# PQ60_EPS_FV4.net
KiCad netlist of a schematic drawn in EAGLE
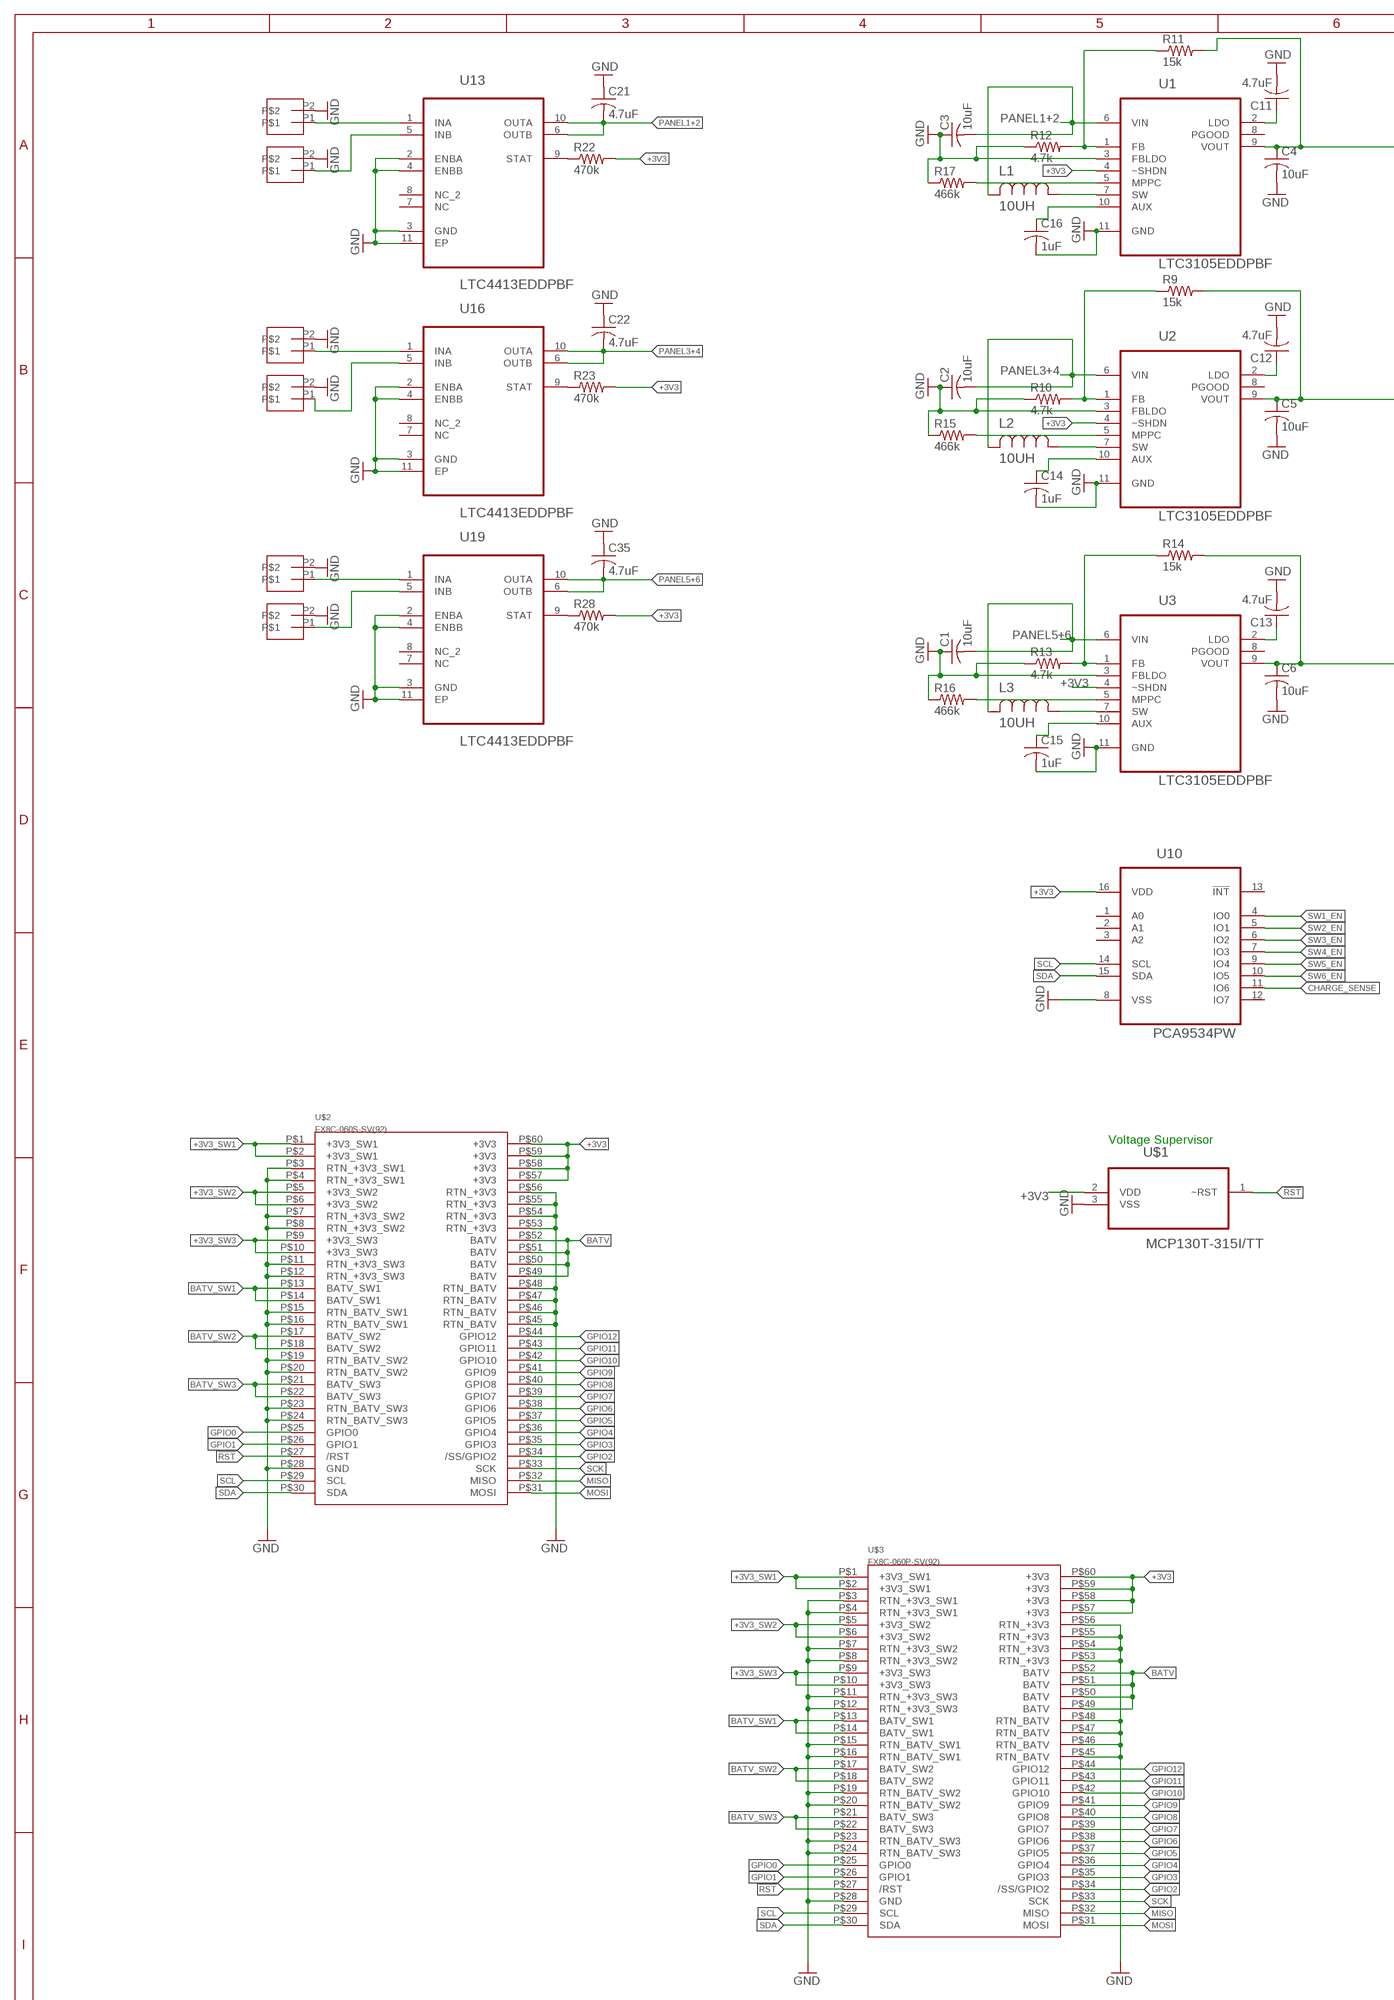
[diagram p0: schematic, sheet 1, part 1 of 2]
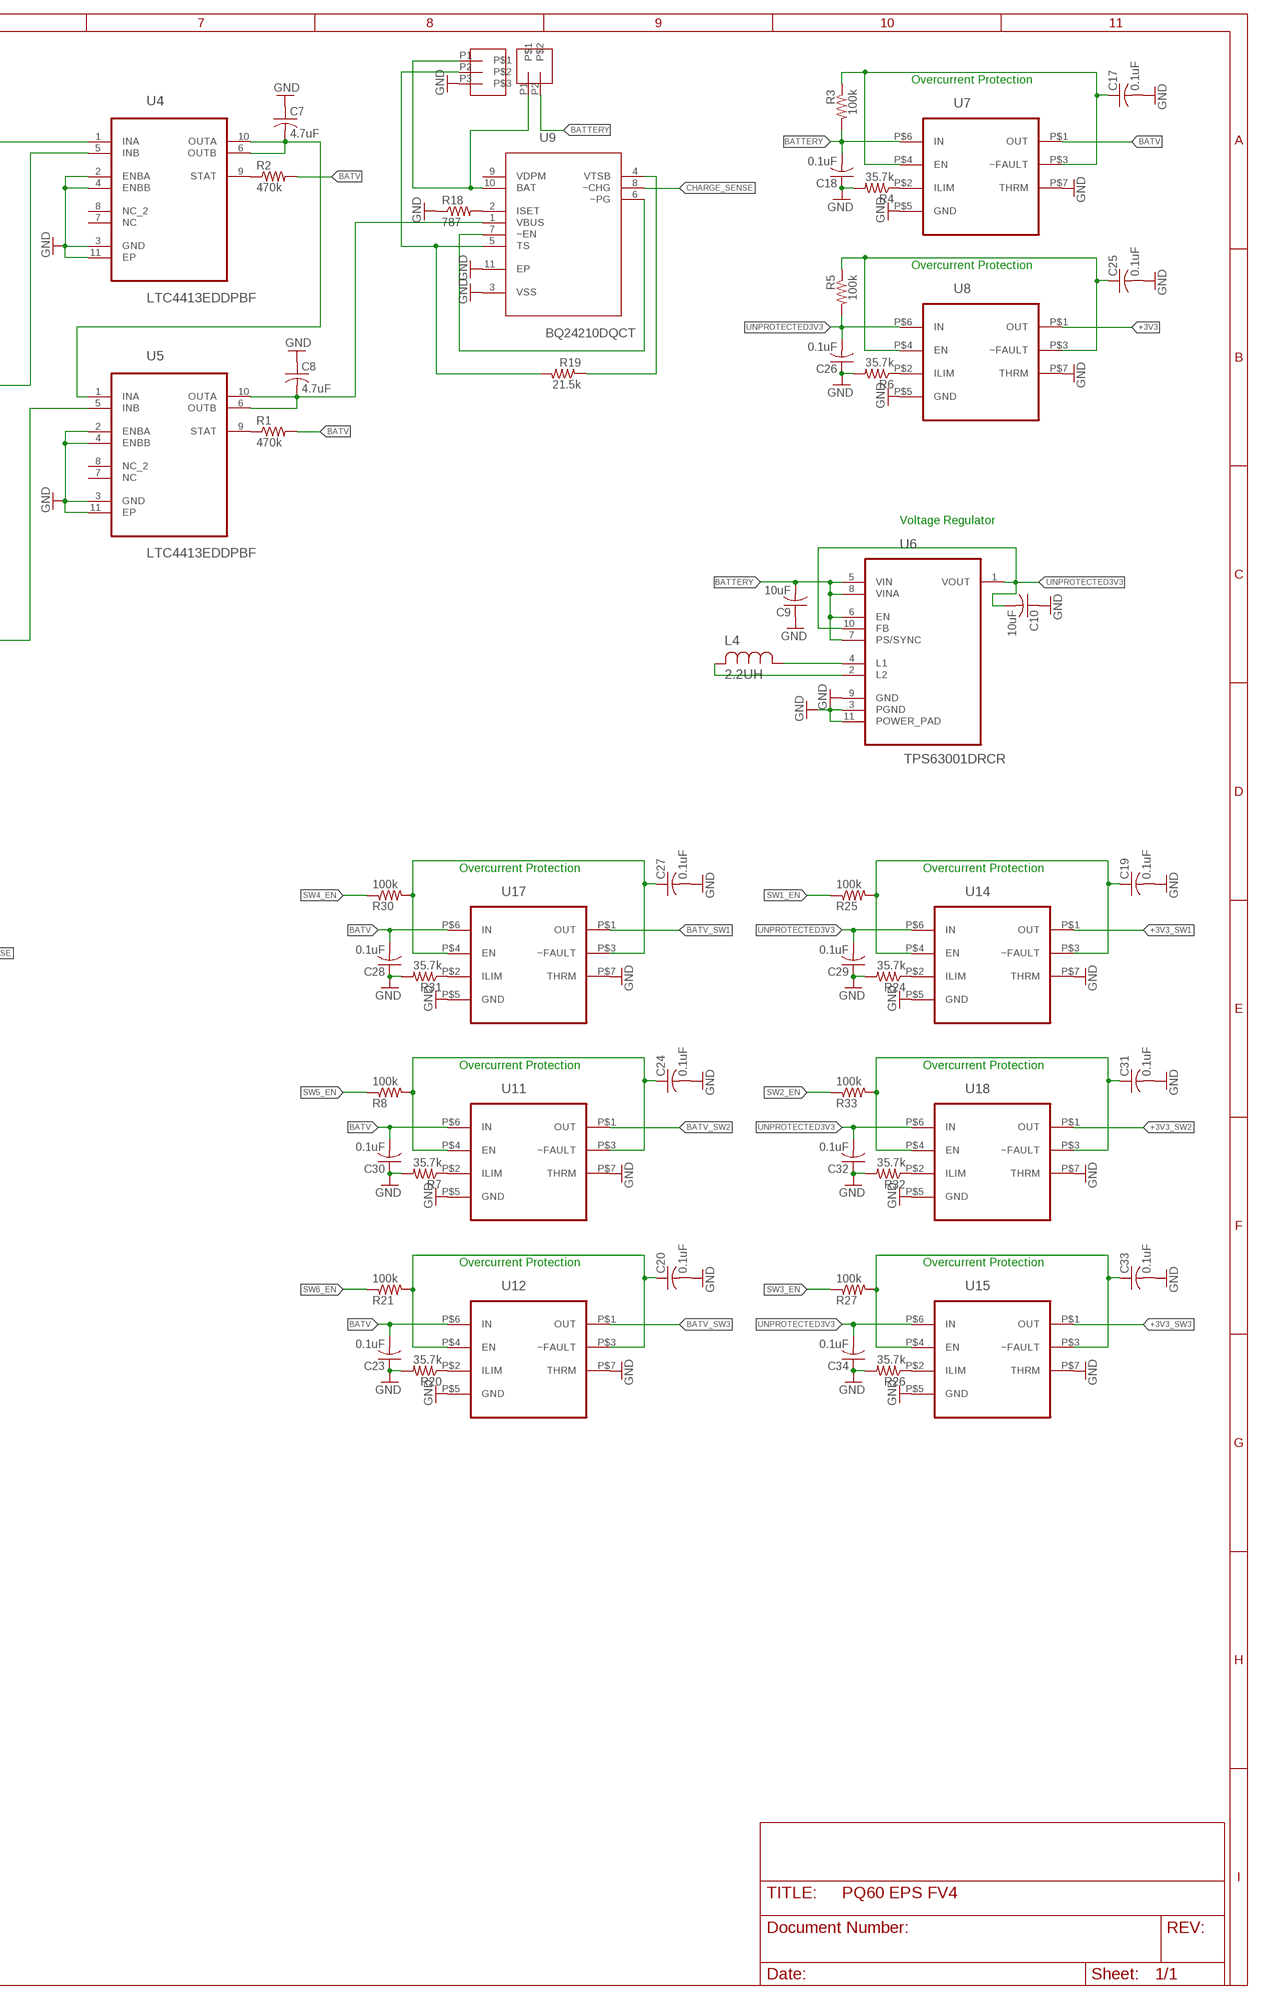
[diagram p1: schematic, sheet 1, part 2 of 2]

(export (version "E")
  (design (tool "Eeschema 10.0.6"))
  (components
    (comp (ref "C1")
      (value "10uF")
      (footprint "eagle-import:C0805")
      (libsource (lib "eagle-import") (part "C-USC0805"))
    )
    (comp (ref "C2")
      (value "10uF")
      (footprint "eagle-import:C0805")
      (libsource (lib "eagle-import") (part "C-USC0805"))
    )
    (comp (ref "C3")
      (value "10uF")
      (footprint "eagle-import:C0805")
      (libsource (lib "eagle-import") (part "C-USC0805"))
    )
    (comp (ref "C4")
      (value "10uF")
      (footprint "eagle-import:C0805")
      (libsource (lib "eagle-import") (part "C-USC0805"))
    )
    (comp (ref "C5")
      (value "10uF")
      (footprint "eagle-import:C0805")
      (libsource (lib "eagle-import") (part "C-USC0805"))
    )
    (comp (ref "C6")
      (value "10uF")
      (footprint "eagle-import:C0805")
      (libsource (lib "eagle-import") (part "C-USC0805"))
    )
    (comp (ref "C7")
      (value "4.7uF")
      (footprint "eagle-import:C0805")
      (libsource (lib "eagle-import") (part "C-USC0805"))
    )
    (comp (ref "C8")
      (value "4.7uF")
      (footprint "eagle-import:C0805")
      (libsource (lib "eagle-import") (part "C-USC0805"))
    )
    (comp (ref "C9")
      (value "10uF")
      (footprint "eagle-import:C0805")
      (libsource (lib "eagle-import") (part "C-USC0805"))
    )
    (comp (ref "C10")
      (value "10uF")
      (footprint "eagle-import:C0805")
      (libsource (lib "eagle-import") (part "C-USC0805"))
    )
    (comp (ref "C11")
      (value "4.7uF")
      (footprint "eagle-import:C0805")
      (libsource (lib "eagle-import") (part "C-USC0805"))
    )
    (comp (ref "C12")
      (value "4.7uF")
      (footprint "eagle-import:C0805")
      (libsource (lib "eagle-import") (part "C-USC0805"))
    )
    (comp (ref "C13")
      (value "4.7uF")
      (footprint "eagle-import:C0805")
      (libsource (lib "eagle-import") (part "C-USC0805"))
    )
    (comp (ref "C14")
      (value "1uF")
      (footprint "eagle-import:C0805")
      (libsource (lib "eagle-import") (part "C-USC0805"))
    )
    (comp (ref "C15")
      (value "1uF")
      (footprint "eagle-import:C0805")
      (libsource (lib "eagle-import") (part "C-USC0805"))
    )
    (comp (ref "C16")
      (value "1uF")
      (footprint "eagle-import:C0805")
      (libsource (lib "eagle-import") (part "C-USC0805"))
    )
    (comp (ref "C17")
      (value "0.1uF")
      (footprint "eagle-import:C0805")
      (libsource (lib "eagle-import") (part "C-USC0805"))
    )
    (comp (ref "C18")
      (value "0.1uF")
      (footprint "eagle-import:C0805")
      (libsource (lib "eagle-import") (part "C-USC0805"))
    )
    (comp (ref "C19")
      (value "0.1uF")
      (footprint "eagle-import:C0805")
      (libsource (lib "eagle-import") (part "C-USC0805"))
    )
    (comp (ref "C20")
      (value "0.1uF")
      (footprint "eagle-import:C0805")
      (libsource (lib "eagle-import") (part "C-USC0805"))
    )
    (comp (ref "C21")
      (value "4.7uF")
      (footprint "eagle-import:C0805")
      (libsource (lib "eagle-import") (part "C-USC0805"))
    )
    (comp (ref "C22")
      (value "4.7uF")
      (footprint "eagle-import:C0805")
      (libsource (lib "eagle-import") (part "C-USC0805"))
    )
    (comp (ref "C23")
      (value "0.1uF")
      (footprint "eagle-import:C0805")
      (libsource (lib "eagle-import") (part "C-USC0805"))
    )
    (comp (ref "C24")
      (value "0.1uF")
      (footprint "eagle-import:C0805")
      (libsource (lib "eagle-import") (part "C-USC0805"))
    )
    (comp (ref "C25")
      (value "0.1uF")
      (footprint "eagle-import:C0805")
      (libsource (lib "eagle-import") (part "C-USC0805"))
    )
    (comp (ref "C26")
      (value "0.1uF")
      (footprint "eagle-import:C0805")
      (libsource (lib "eagle-import") (part "C-USC0805"))
    )
    (comp (ref "C27")
      (value "0.1uF")
      (footprint "eagle-import:C0805")
      (libsource (lib "eagle-import") (part "C-USC0805"))
    )
    (comp (ref "C28")
      (value "0.1uF")
      (footprint "eagle-import:C0805")
      (libsource (lib "eagle-import") (part "C-USC0805"))
    )
    (comp (ref "C29")
      (value "0.1uF")
      (footprint "eagle-import:C0805")
      (libsource (lib "eagle-import") (part "C-USC0805"))
    )
    (comp (ref "C30")
      (value "0.1uF")
      (footprint "eagle-import:C0805")
      (libsource (lib "eagle-import") (part "C-USC0805"))
    )
    (comp (ref "C31")
      (value "0.1uF")
      (footprint "eagle-import:C0805")
      (libsource (lib "eagle-import") (part "C-USC0805"))
    )
    (comp (ref "C32")
      (value "0.1uF")
      (footprint "eagle-import:C0805")
      (libsource (lib "eagle-import") (part "C-USC0805"))
    )
    (comp (ref "C33")
      (value "0.1uF")
      (footprint "eagle-import:C0805")
      (libsource (lib "eagle-import") (part "C-USC0805"))
    )
    (comp (ref "C34")
      (value "0.1uF")
      (footprint "eagle-import:C0805")
      (libsource (lib "eagle-import") (part "C-USC0805"))
    )
    (comp (ref "C35")
      (value "4.7uF")
      (footprint "eagle-import:C0805")
      (libsource (lib "eagle-import") (part "C-USC0805"))
    )
    (comp (ref "L1")
      (value "10UH")
      (footprint "eagle-import:IND_ELL6XH")
      (fields (field (name "MPN") "ELL6SH100M"))
      (libsource (lib "eagle-import") (part "ELL-6XH6SH100M"))
    )
    (comp (ref "L2")
      (value "10UH")
      (footprint "eagle-import:IND_ELL6XH")
      (fields (field (name "MPN") "ELL6SH100M"))
      (libsource (lib "eagle-import") (part "ELL-6XH6SH100M"))
    )
    (comp (ref "L3")
      (value "10UH")
      (footprint "eagle-import:IND_ELL6XH")
      (fields (field (name "MPN") "ELL6SH100M"))
      (libsource (lib "eagle-import") (part "ELL-6XH6SH100M"))
    )
    (comp (ref "L4")
      (value "2.2UH")
      (footprint "eagle-import:IND_ELL3FU")
      (fields (field (name "MPN") "ELL3FU2R2N") (field (name "TOLERANCE") "±30 %"))
      (libsource (lib "eagle-import") (part "ELL-3FU3FU2R2N"))
    )
    (comp (ref "R1")
      (value "470k")
      (footprint "eagle-import:R0805")
      (libsource (lib "eagle-import") (part "R-US_R0805"))
    )
    (comp (ref "R2")
      (value "470k")
      (footprint "eagle-import:R0805")
      (libsource (lib "eagle-import") (part "R-US_R0805"))
    )
    (comp (ref "R3")
      (value "100k")
      (footprint "eagle-import:R0805")
      (libsource (lib "eagle-import") (part "R-US_R0805"))
    )
    (comp (ref "R4")
      (value "35.7k")
      (footprint "eagle-import:R0805")
      (libsource (lib "eagle-import") (part "R-US_R0805"))
    )
    (comp (ref "R5")
      (value "100k")
      (footprint "eagle-import:R0805")
      (libsource (lib "eagle-import") (part "R-US_R0805"))
    )
    (comp (ref "R6")
      (value "35.7k")
      (footprint "eagle-import:R0805")
      (libsource (lib "eagle-import") (part "R-US_R0805"))
    )
    (comp (ref "R7")
      (value "35.7k")
      (footprint "eagle-import:R0805")
      (libsource (lib "eagle-import") (part "R-US_R0805"))
    )
    (comp (ref "R8")
      (value "100k")
      (footprint "eagle-import:R0805")
      (libsource (lib "eagle-import") (part "R-US_R0805"))
    )
    (comp (ref "R9")
      (value "15k")
      (footprint "eagle-import:R0805")
      (libsource (lib "eagle-import") (part "R-US_R0805"))
    )
    (comp (ref "R10")
      (value "4.7k")
      (footprint "eagle-import:R0805")
      (libsource (lib "eagle-import") (part "R-US_R0805"))
    )
    (comp (ref "R11")
      (value "15k")
      (footprint "eagle-import:R0805")
      (libsource (lib "eagle-import") (part "R-US_R0805"))
    )
    (comp (ref "R12")
      (value "4.7k")
      (footprint "eagle-import:R0805")
      (libsource (lib "eagle-import") (part "R-US_R0805"))
    )
    (comp (ref "R13")
      (value "4.7k")
      (footprint "eagle-import:R0805")
      (libsource (lib "eagle-import") (part "R-US_R0805"))
    )
    (comp (ref "R14")
      (value "15k")
      (footprint "eagle-import:R0805")
      (libsource (lib "eagle-import") (part "R-US_R0805"))
    )
    (comp (ref "R15")
      (value "466k")
      (footprint "eagle-import:R0805")
      (libsource (lib "eagle-import") (part "R-US_R0805"))
    )
    (comp (ref "R16")
      (value "466k")
      (footprint "eagle-import:R0805")
      (libsource (lib "eagle-import") (part "R-US_R0805"))
    )
    (comp (ref "R17")
      (value "466k")
      (footprint "eagle-import:R0805")
      (libsource (lib "eagle-import") (part "R-US_R0805"))
    )
    (comp (ref "R18")
      (value "787")
      (footprint "eagle-import:R0805")
      (libsource (lib "eagle-import") (part "R-US_R0805"))
    )
    (comp (ref "R19")
      (value "21.5k")
      (footprint "eagle-import:R0805")
      (libsource (lib "eagle-import") (part "R-US_R0805"))
    )
    (comp (ref "R20")
      (value "35.7k")
      (footprint "eagle-import:R0805")
      (libsource (lib "eagle-import") (part "R-US_R0805"))
    )
    (comp (ref "R21")
      (value "100k")
      (footprint "eagle-import:R0805")
      (libsource (lib "eagle-import") (part "R-US_R0805"))
    )
    (comp (ref "R22")
      (value "470k")
      (footprint "eagle-import:R0805")
      (libsource (lib "eagle-import") (part "R-US_R0805"))
    )
    (comp (ref "R23")
      (value "470k")
      (footprint "eagle-import:R0805")
      (libsource (lib "eagle-import") (part "R-US_R0805"))
    )
    (comp (ref "R24")
      (value "35.7k")
      (footprint "eagle-import:R0805")
      (libsource (lib "eagle-import") (part "R-US_R0805"))
    )
    (comp (ref "R25")
      (value "100k")
      (footprint "eagle-import:R0805")
      (libsource (lib "eagle-import") (part "R-US_R0805"))
    )
    (comp (ref "R26")
      (value "35.7k")
      (footprint "eagle-import:R0805")
      (libsource (lib "eagle-import") (part "R-US_R0805"))
    )
    (comp (ref "R27")
      (value "100k")
      (footprint "eagle-import:R0805")
      (libsource (lib "eagle-import") (part "R-US_R0805"))
    )
    (comp (ref "R28")
      (value "470k")
      (footprint "eagle-import:R0805")
      (libsource (lib "eagle-import") (part "R-US_R0805"))
    )
    (comp (ref "R30")
      (value "100k")
      (footprint "eagle-import:R0805")
      (libsource (lib "eagle-import") (part "R-US_R0805"))
    )
    (comp (ref "R31")
      (value "35.7k")
      (footprint "eagle-import:R0805")
      (libsource (lib "eagle-import") (part "R-US_R0805"))
    )
    (comp (ref "R32")
      (value "35.7k")
      (footprint "eagle-import:R0805")
      (libsource (lib "eagle-import") (part "R-US_R0805"))
    )
    (comp (ref "R33")
      (value "100k")
      (footprint "eagle-import:R0805")
      (libsource (lib "eagle-import") (part "R-US_R0805"))
    )
    (comp (ref "U$1")
      (value "MCP130T-315I/TT")
      (footprint "eagle-import:SOT95P237X112-3N")
      (libsource (lib "eagle-import") (part "MCP130T-315I/TT"))
    )
    (comp (ref "U$2")
      (value "FX8C-060S-SV(92)")
      (footprint "eagle-import:FX8C-060S-SV(92)")
      (libsource (lib "eagle-import") (part "FX8C-060S-SV(92)"))
    )
    (comp (ref "U$3")
      (value "FX8C-060P-SV(92)")
      (footprint "eagle-import:FX8C-060P-SV(92)")
      (libsource (lib "eagle-import") (part "FX8C-060P-SV(92)"))
    )
    (comp (ref "U$4")
      (value "JST-SH-02")
      (footprint "eagle-import:JST-SH-02")
      (libsource (lib "eagle-import") (part "JST-SH-02"))
    )
    (comp (ref "U$5")
      (value "JST-SH-02")
      (footprint "eagle-import:JST-SH-02")
      (libsource (lib "eagle-import") (part "JST-SH-02"))
    )
    (comp (ref "U$6")
      (value "JST-SH-02")
      (footprint "eagle-import:JST-SH-02")
      (libsource (lib "eagle-import") (part "JST-SH-02"))
    )
    (comp (ref "U$7")
      (value "JST-SH-02")
      (footprint "eagle-import:JST-SH-02")
      (libsource (lib "eagle-import") (part "JST-SH-02"))
    )
    (comp (ref "U$8")
      (value "JST-SH-02")
      (footprint "eagle-import:JST-SH-02")
      (libsource (lib "eagle-import") (part "JST-SH-02"))
    )
    (comp (ref "U$9")
      (value "JST-SH-02")
      (footprint "eagle-import:JST-SH-02")
      (libsource (lib "eagle-import") (part "JST-SH-02"))
    )
    (comp (ref "U$10")
      (value "JST-SH-02")
      (footprint "eagle-import:JST-SH-02")
      (libsource (lib "eagle-import") (part "JST-SH-02"))
    )
    (comp (ref "U$11")
      (value "JST-SH-03")
      (footprint "eagle-import:JST-SH-03")
      (libsource (lib "eagle-import") (part "JST-SH-03"))
    )
    (comp (ref "U1")
      (value "LTC3105EDDPBF")
      (footprint "eagle-import:DFN300X300X80-11N")
      (fields (field (name "MPN") "LTC3105EDD#PBF"))
      (libsource (lib "eagle-import") (part "LTC3105EDDPBF"))
    )
    (comp (ref "U2")
      (value "LTC3105EDDPBF")
      (footprint "eagle-import:DFN300X300X80-11N")
      (fields (field (name "MPN") "LTC3105EDD#PBF"))
      (libsource (lib "eagle-import") (part "LTC3105EDDPBF"))
    )
    (comp (ref "U3")
      (value "LTC3105EDDPBF")
      (footprint "eagle-import:DFN300X300X80-11N")
      (fields (field (name "MPN") "LTC3105EDD#PBF"))
      (libsource (lib "eagle-import") (part "LTC3105EDDPBF"))
    )
    (comp (ref "U4")
      (value "LTC4413EDDPBF")
      (footprint "eagle-import:DFN300X300X80-11N")
      (fields (field (name "MPN") "LTC4413EDD#PBF"))
      (libsource (lib "eagle-import") (part "LTC4413EDDPBF"))
    )
    (comp (ref "U5")
      (value "LTC4413EDDPBF")
      (footprint "eagle-import:DFN300X300X80-11N")
      (fields (field (name "MPN") "LTC4413EDD#PBF"))
      (libsource (lib "eagle-import") (part "LTC4413EDDPBF"))
    )
    (comp (ref "U6")
      (value "TPS63001DRCR")
      (footprint "eagle-import:SON50P300X300X100-11N")
      (libsource (lib "eagle-import") (part "TPS63001DRCR"))
    )
    (comp (ref "U7")
      (value "DRV")
      (footprint "eagle-import:DRV")
      (libsource (lib "eagle-import") (part "DRV"))
    )
    (comp (ref "U8")
      (value "DRV")
      (footprint "eagle-import:DRV")
      (libsource (lib "eagle-import") (part "DRV"))
    )
    (comp (ref "U9")
      (value "BQ24210DQCT")
      (footprint "eagle-import:SON50P200X300X80-11N")
      (libsource (lib "eagle-import") (part "BQ24210DQCT"))
    )
    (comp (ref "U10")
      (value "PCA9534PW")
      (footprint "eagle-import:SOP65P640X110-16N")
      (libsource (lib "eagle-import") (part "PCA9534PW"))
    )
    (comp (ref "U11")
      (value "DRV")
      (footprint "eagle-import:DRV")
      (libsource (lib "eagle-import") (part "DRV"))
    )
    (comp (ref "U12")
      (value "DRV")
      (footprint "eagle-import:DRV")
      (libsource (lib "eagle-import") (part "DRV"))
    )
    (comp (ref "U13")
      (value "LTC4413EDDPBF")
      (footprint "eagle-import:DFN300X300X80-11N")
      (fields (field (name "MPN") "LTC4413EDD#PBF"))
      (libsource (lib "eagle-import") (part "LTC4413EDDPBF"))
    )
    (comp (ref "U14")
      (value "DRV")
      (footprint "eagle-import:DRV")
      (libsource (lib "eagle-import") (part "DRV"))
    )
    (comp (ref "U15")
      (value "DRV")
      (footprint "eagle-import:DRV")
      (libsource (lib "eagle-import") (part "DRV"))
    )
    (comp (ref "U16")
      (value "LTC4413EDDPBF")
      (footprint "eagle-import:DFN300X300X80-11N")
      (fields (field (name "MPN") "LTC4413EDD#PBF"))
      (libsource (lib "eagle-import") (part "LTC4413EDDPBF"))
    )
    (comp (ref "U17")
      (value "DRV")
      (footprint "eagle-import:DRV")
      (libsource (lib "eagle-import") (part "DRV"))
    )
    (comp (ref "U18")
      (value "DRV")
      (footprint "eagle-import:DRV")
      (libsource (lib "eagle-import") (part "DRV"))
    )
    (comp (ref "U19")
      (value "LTC4413EDDPBF")
      (footprint "eagle-import:DFN300X300X80-11N")
      (fields (field (name "MPN") "LTC4413EDD#PBF"))
      (libsource (lib "eagle-import") (part "LTC4413EDDPBF"))
    )
  )
  (nets
    (net (code "1") (name "+3V3") (class "Default")
      (node (ref "R22") (pin "2") (pinfunction "2_2") (pintype "passive"))
      (node (ref "R23") (pin "2") (pinfunction "2_2") (pintype "passive"))
      (node (ref "R28") (pin "2") (pinfunction "2_2") (pintype "passive"))
      (node (ref "U$1") (pin "2") (pinfunction "VDD_2") (pintype "power_in"))
      (node (ref "U$2") (pin "P$57") (pinfunction "+3V3_P$57") (pintype "power_in"))
      (node (ref "U$2") (pin "P$58") (pinfunction "+3V3_P$58") (pintype "power_in"))
      (node (ref "U$2") (pin "P$59") (pinfunction "+3V3_P$59") (pintype "power_in"))
      (node (ref "U$2") (pin "P$60") (pinfunction "+3V3_P$60") (pintype "power_in"))
      (node (ref "U$3") (pin "P$57") (pinfunction "+3V3_P$57") (pintype "power_in"))
      (node (ref "U$3") (pin "P$58") (pinfunction "+3V3_P$58") (pintype "power_in"))
      (node (ref "U$3") (pin "P$59") (pinfunction "+3V3_P$59") (pintype "power_in"))
      (node (ref "U$3") (pin "P$60") (pinfunction "+3V3_P$60") (pintype "power_in"))
      (node (ref "U1") (pin "4") (pinfunction "~{SHDN}_4") (pintype "input"))
      (node (ref "U10") (pin "16") (pinfunction "VDD_16") (pintype "power_in"))
      (node (ref "U2") (pin "4") (pinfunction "~{SHDN}_4") (pintype "input"))
      (node (ref "U3") (pin "4") (pinfunction "~{SHDN}_4") (pintype "input"))
      (node (ref "U8") (pin "P$1") (pinfunction "OUT_P$1") (pintype "output"))
    )
    (net (code "2") (name "+3V3_SW1") (class "Default")
      (node (ref "U$2") (pin "P$1") (pinfunction "+3V3_SW1_P$1") (pintype "power_in"))
      (node (ref "U$2") (pin "P$2") (pinfunction "+3V3_SW1_P$2") (pintype "power_in"))
      (node (ref "U$3") (pin "P$1") (pinfunction "+3V3_SW1_P$1") (pintype "power_in"))
      (node (ref "U$3") (pin "P$2") (pinfunction "+3V3_SW1_P$2") (pintype "power_in"))
      (node (ref "U14") (pin "P$1") (pinfunction "OUT_P$1") (pintype "output"))
    )
    (net (code "3") (name "+3V3_SW2") (class "Default")
      (node (ref "U$2") (pin "P$5") (pinfunction "+3V3_SW2_P$5") (pintype "power_in"))
      (node (ref "U$2") (pin "P$6") (pinfunction "+3V3_SW2_P$6") (pintype "power_in"))
      (node (ref "U$3") (pin "P$5") (pinfunction "+3V3_SW2_P$5") (pintype "power_in"))
      (node (ref "U$3") (pin "P$6") (pinfunction "+3V3_SW2_P$6") (pintype "power_in"))
      (node (ref "U18") (pin "P$1") (pinfunction "OUT_P$1") (pintype "output"))
    )
    (net (code "4") (name "+3V3_SW3") (class "Default")
      (node (ref "U$2") (pin "P$10") (pinfunction "+3V3_SW3_P$10") (pintype "power_in"))
      (node (ref "U$2") (pin "P$9") (pinfunction "+3V3_SW3_P$9") (pintype "power_in"))
      (node (ref "U$3") (pin "P$10") (pinfunction "+3V3_SW3_P$10") (pintype "power_in"))
      (node (ref "U$3") (pin "P$9") (pinfunction "+3V3_SW3_P$9") (pintype "power_in"))
      (node (ref "U15") (pin "P$1") (pinfunction "OUT_P$1") (pintype "output"))
    )
    (net (code "5") (name "/~{RST}") (class "Default")
      (node (ref "U$1") (pin "1") (pinfunction "~{RST}_1") (pintype "output"))
      (node (ref "U$2") (pin "P$27") (pinfunction "/RST_P$27") (pintype "bidirectional"))
      (node (ref "U$3") (pin "P$27") (pinfunction "/RST_P$27") (pintype "bidirectional"))
    )
    (net (code "6") (name "BATTERY") (class "Default")
      (node (ref "C18") (pin "2") (pinfunction "2_2") (pintype "passive"))
      (node (ref "C9") (pin "2") (pinfunction "2_2") (pintype "passive"))
      (node (ref "R3") (pin "2") (pinfunction "2_2") (pintype "passive"))
      (node (ref "U$10") (pin "P2") (pinfunction "P$2_P2") (pintype "bidirectional"))
      (node (ref "U6") (pin "5") (pinfunction "VIN_5") (pintype "power_in"))
      (node (ref "U6") (pin "6") (pinfunction "EN_6") (pintype "input"))
      (node (ref "U6") (pin "7") (pinfunction "PS/SYNC_7") (pintype "input"))
      (node (ref "U6") (pin "8") (pinfunction "VINA_8") (pintype "power_in"))
      (node (ref "U7") (pin "P$6") (pinfunction "IN_P$6") (pintype "power_in"))
    )
    (net (code "7") (name "BATV") (class "Default")
      (node (ref "C23") (pin "2") (pinfunction "2_2") (pintype "passive"))
      (node (ref "C28") (pin "2") (pinfunction "2_2") (pintype "passive"))
      (node (ref "C30") (pin "2") (pinfunction "2_2") (pintype "passive"))
      (node (ref "R1") (pin "2") (pinfunction "2_2") (pintype "passive"))
      (node (ref "R2") (pin "2") (pinfunction "2_2") (pintype "passive"))
      (node (ref "U$2") (pin "P$49") (pinfunction "BATV_P$49") (pintype "power_in"))
      (node (ref "U$2") (pin "P$50") (pinfunction "BATV_P$50") (pintype "power_in"))
      (node (ref "U$2") (pin "P$51") (pinfunction "BATV_P$51") (pintype "power_in"))
      (node (ref "U$2") (pin "P$52") (pinfunction "BATV_P$52") (pintype "power_in"))
      (node (ref "U$3") (pin "P$49") (pinfunction "BATV_P$49") (pintype "power_in"))
      (node (ref "U$3") (pin "P$50") (pinfunction "BATV_P$50") (pintype "power_in"))
      (node (ref "U$3") (pin "P$51") (pinfunction "BATV_P$51") (pintype "power_in"))
      (node (ref "U$3") (pin "P$52") (pinfunction "BATV_P$52") (pintype "power_in"))
      (node (ref "U11") (pin "P$6") (pinfunction "IN_P$6") (pintype "power_in"))
      (node (ref "U12") (pin "P$6") (pinfunction "IN_P$6") (pintype "power_in"))
      (node (ref "U17") (pin "P$6") (pinfunction "IN_P$6") (pintype "power_in"))
      (node (ref "U7") (pin "P$1") (pinfunction "OUT_P$1") (pintype "output"))
    )
    (net (code "8") (name "BATV_SW1") (class "Default")
      (node (ref "U$2") (pin "P$13") (pinfunction "BATV_SW1_P$13") (pintype "power_in"))
      (node (ref "U$2") (pin "P$14") (pinfunction "BATV_SW1_P$14") (pintype "power_in"))
      (node (ref "U$3") (pin "P$13") (pinfunction "BATV_SW1_P$13") (pintype "power_in"))
      (node (ref "U$3") (pin "P$14") (pinfunction "BATV_SW1_P$14") (pintype "power_in"))
      (node (ref "U17") (pin "P$1") (pinfunction "OUT_P$1") (pintype "output"))
    )
    (net (code "9") (name "BATV_SW2") (class "Default")
      (node (ref "U$2") (pin "P$17") (pinfunction "BATV_SW2_P$17") (pintype "power_in"))
      (node (ref "U$2") (pin "P$18") (pinfunction "BATV_SW2_P$18") (pintype "power_in"))
      (node (ref "U$3") (pin "P$17") (pinfunction "BATV_SW2_P$17") (pintype "power_in"))
      (node (ref "U$3") (pin "P$18") (pinfunction "BATV_SW2_P$18") (pintype "power_in"))
      (node (ref "U11") (pin "P$1") (pinfunction "OUT_P$1") (pintype "output"))
    )
    (net (code "10") (name "BATV_SW3") (class "Default")
      (node (ref "U$2") (pin "P$21") (pinfunction "BATV_SW3_P$21") (pintype "power_in"))
      (node (ref "U$2") (pin "P$22") (pinfunction "BATV_SW3_P$22") (pintype "power_in"))
      (node (ref "U$3") (pin "P$21") (pinfunction "BATV_SW3_P$21") (pintype "power_in"))
      (node (ref "U$3") (pin "P$22") (pinfunction "BATV_SW3_P$22") (pintype "power_in"))
      (node (ref "U12") (pin "P$1") (pinfunction "OUT_P$1") (pintype "output"))
    )
    (net (code "11") (name "CHARGE_SENSE") (class "Default")
      (node (ref "U10") (pin "11") (pinfunction "IO6_11") (pintype "bidirectional"))
      (node (ref "U9") (pin "8") (pinfunction "~{CHG}_8") (pintype "output"))
    )
    (net (code "12") (name "GND") (class "Default")
      (node (ref "C1") (pin "1") (pinfunction "1_1") (pintype "passive"))
      (node (ref "C10") (pin "1") (pinfunction "1_1") (pintype "passive"))
      (node (ref "C11") (pin "2") (pinfunction "2_2") (pintype "passive"))
      (node (ref "C12") (pin "2") (pinfunction "2_2") (pintype "passive"))
      (node (ref "C13") (pin "2") (pinfunction "2_2") (pintype "passive"))
      (node (ref "C14") (pin "2") (pinfunction "2_2") (pintype "passive"))
      (node (ref "C15") (pin "2") (pinfunction "2_2") (pintype "passive"))
      (node (ref "C16") (pin "2") (pinfunction "2_2") (pintype "passive"))
      (node (ref "C17") (pin "2") (pinfunction "2_2") (pintype "passive"))
      (node (ref "C18") (pin "1") (pinfunction "1_1") (pintype "passive"))
      (node (ref "C19") (pin "2") (pinfunction "2_2") (pintype "passive"))
      (node (ref "C2") (pin "1") (pinfunction "1_1") (pintype "passive"))
      (node (ref "C20") (pin "2") (pinfunction "2_2") (pintype "passive"))
      (node (ref "C21") (pin "1") (pinfunction "1_1") (pintype "passive"))
      (node (ref "C22") (pin "1") (pinfunction "1_1") (pintype "passive"))
      (node (ref "C23") (pin "1") (pinfunction "1_1") (pintype "passive"))
      (node (ref "C24") (pin "2") (pinfunction "2_2") (pintype "passive"))
      (node (ref "C25") (pin "2") (pinfunction "2_2") (pintype "passive"))
      (node (ref "C26") (pin "1") (pinfunction "1_1") (pintype "passive"))
      (node (ref "C27") (pin "2") (pinfunction "2_2") (pintype "passive"))
      (node (ref "C28") (pin "1") (pinfunction "1_1") (pintype "passive"))
      (node (ref "C29") (pin "1") (pinfunction "1_1") (pintype "passive"))
      (node (ref "C3") (pin "1") (pinfunction "1_1") (pintype "passive"))
      (node (ref "C30") (pin "1") (pinfunction "1_1") (pintype "passive"))
      (node (ref "C31") (pin "2") (pinfunction "2_2") (pintype "passive"))
      (node (ref "C32") (pin "1") (pinfunction "1_1") (pintype "passive"))
      (node (ref "C33") (pin "2") (pinfunction "2_2") (pintype "passive"))
      (node (ref "C34") (pin "1") (pinfunction "1_1") (pintype "passive"))
      (node (ref "C35") (pin "1") (pinfunction "1_1") (pintype "passive"))
      (node (ref "C4") (pin "2") (pinfunction "2_2") (pintype "passive"))
      (node (ref "C5") (pin "2") (pinfunction "2_2") (pintype "passive"))
      (node (ref "C6") (pin "2") (pinfunction "2_2") (pintype "passive"))
      (node (ref "C7") (pin "1") (pinfunction "1_1") (pintype "passive"))
      (node (ref "C8") (pin "1") (pinfunction "1_1") (pintype "passive"))
      (node (ref "C9") (pin "1") (pinfunction "1_1") (pintype "passive"))
      (node (ref "R10") (pin "1") (pinfunction "1_1") (pintype "passive"))
      (node (ref "R12") (pin "1") (pinfunction "1_1") (pintype "passive"))
      (node (ref "R13") (pin "1") (pinfunction "1_1") (pintype "passive"))
      (node (ref "R15") (pin "1") (pinfunction "1_1") (pintype "passive"))
      (node (ref "R16") (pin "1") (pinfunction "1_1") (pintype "passive"))
      (node (ref "R17") (pin "1") (pinfunction "1_1") (pintype "passive"))
      (node (ref "R18") (pin "1") (pinfunction "1_1") (pintype "passive"))
      (node (ref "R20") (pin "2") (pinfunction "2_2") (pintype "passive"))
      (node (ref "R24") (pin "2") (pinfunction "2_2") (pintype "passive"))
      (node (ref "R26") (pin "2") (pinfunction "2_2") (pintype "passive"))
      (node (ref "R31") (pin "2") (pinfunction "2_2") (pintype "passive"))
      (node (ref "R32") (pin "2") (pinfunction "2_2") (pintype "passive"))
      (node (ref "R4") (pin "2") (pinfunction "2_2") (pintype "passive"))
      (node (ref "R6") (pin "2") (pinfunction "2_2") (pintype "passive"))
      (node (ref "R7") (pin "2") (pinfunction "2_2") (pintype "passive"))
      (node (ref "U$1") (pin "3") (pinfunction "VSS_3") (pintype "power_in"))
      (node (ref "U$11") (pin "P3") (pinfunction "P$3_P3") (pintype "bidirectional"))
      (node (ref "U$2") (pin "P$11") (pinfunction "RTN_+3V3_SW3_P$11") (pintype "power_in"))
      (node (ref "U$2") (pin "P$12") (pinfunction "RTN_+3V3_SW3_P$12") (pintype "power_in"))
      (node (ref "U$2") (pin "P$15") (pinfunction "RTN_BATV_SW1_P$15") (pintype "power_in"))
      (node (ref "U$2") (pin "P$16") (pinfunction "RTN_BATV_SW1_P$16") (pintype "power_in"))
      (node (ref "U$2") (pin "P$19") (pinfunction "RTN_BATV_SW2_P$19") (pintype "power_in"))
      (node (ref "U$2") (pin "P$20") (pinfunction "RTN_BATV_SW2_P$20") (pintype "power_in"))
      (node (ref "U$2") (pin "P$23") (pinfunction "RTN_BATV_SW3_P$23") (pintype "power_in"))
      (node (ref "U$2") (pin "P$24") (pinfunction "RTN_BATV_SW3_P$24") (pintype "power_in"))
      (node (ref "U$2") (pin "P$28") (pinfunction "GND_P$28") (pintype "bidirectional"))
      (node (ref "U$2") (pin "P$3") (pinfunction "RTN_+3V3_SW1_P$3") (pintype "power_in"))
      (node (ref "U$2") (pin "P$4") (pinfunction "RTN_+3V3_SW1_P$4") (pintype "power_in"))
      (node (ref "U$2") (pin "P$45") (pinfunction "RTN_BATV_P$45") (pintype "power_in"))
      (node (ref "U$2") (pin "P$46") (pinfunction "RTN_BATV_P$46") (pintype "power_in"))
      (node (ref "U$2") (pin "P$47") (pinfunction "RTN_BATV_P$47") (pintype "power_in"))
      (node (ref "U$2") (pin "P$48") (pinfunction "RTN_BATV_P$48") (pintype "power_in"))
      (node (ref "U$2") (pin "P$53") (pinfunction "RTN_+3V3_P$53") (pintype "power_in"))
      (node (ref "U$2") (pin "P$54") (pinfunction "RTN_+3V3_P$54") (pintype "power_in"))
      (node (ref "U$2") (pin "P$55") (pinfunction "RTN_+3V3_P$55") (pintype "power_in"))
      (node (ref "U$2") (pin "P$56") (pinfunction "RTN_+3V3_P$56") (pintype "power_in"))
      (node (ref "U$2") (pin "P$7") (pinfunction "RTN_+3V3_SW2_P$7") (pintype "power_in"))
      (node (ref "U$2") (pin "P$8") (pinfunction "RTN_+3V3_SW2_P$8") (pintype "power_in"))
      (node (ref "U$3") (pin "P$11") (pinfunction "RTN_+3V3_SW3_P$11") (pintype "power_in"))
      (node (ref "U$3") (pin "P$12") (pinfunction "RTN_+3V3_SW3_P$12") (pintype "power_in"))
      (node (ref "U$3") (pin "P$15") (pinfunction "RTN_BATV_SW1_P$15") (pintype "power_in"))
      (node (ref "U$3") (pin "P$16") (pinfunction "RTN_BATV_SW1_P$16") (pintype "power_in"))
      (node (ref "U$3") (pin "P$19") (pinfunction "RTN_BATV_SW2_P$19") (pintype "power_in"))
      (node (ref "U$3") (pin "P$20") (pinfunction "RTN_BATV_SW2_P$20") (pintype "power_in"))
      (node (ref "U$3") (pin "P$23") (pinfunction "RTN_BATV_SW3_P$23") (pintype "power_in"))
      (node (ref "U$3") (pin "P$24") (pinfunction "RTN_BATV_SW3_P$24") (pintype "power_in"))
      (node (ref "U$3") (pin "P$28") (pinfunction "GND_P$28") (pintype "bidirectional"))
      (node (ref "U$3") (pin "P$3") (pinfunction "RTN_+3V3_SW1_P$3") (pintype "power_in"))
      (node (ref "U$3") (pin "P$4") (pinfunction "RTN_+3V3_SW1_P$4") (pintype "power_in"))
      (node (ref "U$3") (pin "P$45") (pinfunction "RTN_BATV_P$45") (pintype "power_in"))
      (node (ref "U$3") (pin "P$46") (pinfunction "RTN_BATV_P$46") (pintype "power_in"))
      (node (ref "U$3") (pin "P$47") (pinfunction "RTN_BATV_P$47") (pintype "power_in"))
      (node (ref "U$3") (pin "P$48") (pinfunction "RTN_BATV_P$48") (pintype "power_in"))
      (node (ref "U$3") (pin "P$53") (pinfunction "RTN_+3V3_P$53") (pintype "power_in"))
      (node (ref "U$3") (pin "P$54") (pinfunction "RTN_+3V3_P$54") (pintype "power_in"))
      (node (ref "U$3") (pin "P$55") (pinfunction "RTN_+3V3_P$55") (pintype "power_in"))
      (node (ref "U$3") (pin "P$56") (pinfunction "RTN_+3V3_P$56") (pintype "power_in"))
      (node (ref "U$3") (pin "P$7") (pinfunction "RTN_+3V3_SW2_P$7") (pintype "power_in"))
      (node (ref "U$3") (pin "P$8") (pinfunction "RTN_+3V3_SW2_P$8") (pintype "power_in"))
      (node (ref "U$4") (pin "P2") (pinfunction "P$2_P2") (pintype "bidirectional"))
      (node (ref "U$5") (pin "P2") (pinfunction "P$2_P2") (pintype "bidirectional"))
      (node (ref "U$6") (pin "P2") (pinfunction "P$2_P2") (pintype "bidirectional"))
      (node (ref "U$7") (pin "P2") (pinfunction "P$2_P2") (pintype "bidirectional"))
      (node (ref "U$8") (pin "P2") (pinfunction "P$2_P2") (pintype "bidirectional"))
      (node (ref "U$9") (pin "P2") (pinfunction "P$2_P2") (pintype "bidirectional"))
      (node (ref "U1") (pin "11") (pinfunction "GND_11") (pintype "passive"))
      (node (ref "U1") (pin "3") (pinfunction "FBLDO_3") (pintype "input"))
      (node (ref "U10") (pin "8") (pinfunction "VSS_8") (pintype "passive"))
      (node (ref "U11") (pin "P$5") (pinfunction "GND_P$5") (pintype "passive"))
      (node (ref "U11") (pin "P$7") (pinfunction "THRM_P$7") (pintype "bidirectional"))
      (node (ref "U12") (pin "P$5") (pinfunction "GND_P$5") (pintype "passive"))
      (node (ref "U12") (pin "P$7") (pinfunction "THRM_P$7") (pintype "bidirectional"))
      (node (ref "U13") (pin "11") (pinfunction "EP_11") (pintype "passive"))
      (node (ref "U13") (pin "2") (pinfunction "ENBA_2") (pintype "input"))
      (node (ref "U13") (pin "3") (pinfunction "GND_3") (pintype "passive"))
      (node (ref "U13") (pin "4") (pinfunction "ENBB_4") (pintype "input"))
      (node (ref "U14") (pin "P$5") (pinfunction "GND_P$5") (pintype "passive"))
      (node (ref "U14") (pin "P$7") (pinfunction "THRM_P$7") (pintype "bidirectional"))
      (node (ref "U15") (pin "P$5") (pinfunction "GND_P$5") (pintype "passive"))
      (node (ref "U15") (pin "P$7") (pinfunction "THRM_P$7") (pintype "bidirectional"))
      (node (ref "U16") (pin "11") (pinfunction "EP_11") (pintype "passive"))
      (node (ref "U16") (pin "2") (pinfunction "ENBA_2") (pintype "input"))
      (node (ref "U16") (pin "3") (pinfunction "GND_3") (pintype "passive"))
      (node (ref "U16") (pin "4") (pinfunction "ENBB_4") (pintype "input"))
      (node (ref "U17") (pin "P$5") (pinfunction "GND_P$5") (pintype "passive"))
      (node (ref "U17") (pin "P$7") (pinfunction "THRM_P$7") (pintype "bidirectional"))
      (node (ref "U18") (pin "P$5") (pinfunction "GND_P$5") (pintype "passive"))
      (node (ref "U18") (pin "P$7") (pinfunction "THRM_P$7") (pintype "bidirectional"))
      (node (ref "U19") (pin "11") (pinfunction "EP_11") (pintype "passive"))
      (node (ref "U19") (pin "2") (pinfunction "ENBA_2") (pintype "input"))
      (node (ref "U19") (pin "3") (pinfunction "GND_3") (pintype "passive"))
      (node (ref "U19") (pin "4") (pinfunction "ENBB_4") (pintype "input"))
      (node (ref "U2") (pin "11") (pinfunction "GND_11") (pintype "passive"))
      (node (ref "U2") (pin "3") (pinfunction "FBLDO_3") (pintype "input"))
      (node (ref "U3") (pin "11") (pinfunction "GND_11") (pintype "passive"))
      (node (ref "U3") (pin "3") (pinfunction "FBLDO_3") (pintype "input"))
      (node (ref "U4") (pin "11") (pinfunction "EP_11") (pintype "passive"))
      (node (ref "U4") (pin "2") (pinfunction "ENBA_2") (pintype "input"))
      (node (ref "U4") (pin "3") (pinfunction "GND_3") (pintype "passive"))
      (node (ref "U4") (pin "4") (pinfunction "ENBB_4") (pintype "input"))
      (node (ref "U5") (pin "11") (pinfunction "EP_11") (pintype "passive"))
      (node (ref "U5") (pin "2") (pinfunction "ENBA_2") (pintype "input"))
      (node (ref "U5") (pin "3") (pinfunction "GND_3") (pintype "passive"))
      (node (ref "U5") (pin "4") (pinfunction "ENBB_4") (pintype "input"))
      (node (ref "U6") (pin "11") (pinfunction "POWER_PAD_11") (pintype "passive"))
      (node (ref "U6") (pin "3") (pinfunction "PGND_3") (pintype "passive"))
      (node (ref "U6") (pin "9") (pinfunction "GND_9") (pintype "passive"))
      (node (ref "U7") (pin "P$5") (pinfunction "GND_P$5") (pintype "passive"))
      (node (ref "U7") (pin "P$7") (pinfunction "THRM_P$7") (pintype "bidirectional"))
      (node (ref "U8") (pin "P$5") (pinfunction "GND_P$5") (pintype "passive"))
      (node (ref "U8") (pin "P$7") (pinfunction "THRM_P$7") (pintype "bidirectional"))
      (node (ref "U9") (pin "11") (pinfunction "EP_11") (pintype "passive"))
      (node (ref "U9") (pin "3") (pinfunction "VSS_3") (pintype "passive"))
    )
    (net (code "13") (name "GPIO0") (class "Default")
      (node (ref "U$2") (pin "P$25") (pinfunction "GPIO0_P$25") (pintype "bidirectional"))
      (node (ref "U$3") (pin "P$25") (pinfunction "GPIO0_P$25") (pintype "bidirectional"))
    )
    (net (code "14") (name "GPIO1") (class "Default")
      (node (ref "U$2") (pin "P$26") (pinfunction "GPIO1_P$26") (pintype "bidirectional"))
      (node (ref "U$3") (pin "P$26") (pinfunction "GPIO1_P$26") (pintype "bidirectional"))
    )
    (net (code "15") (name "GPIO2") (class "Default")
      (node (ref "U$2") (pin "P$34") (pinfunction "/SS/GPIO2_P$34") (pintype "bidirectional"))
      (node (ref "U$3") (pin "P$34") (pinfunction "/SS/GPIO2_P$34") (pintype "bidirectional"))
    )
    (net (code "16") (name "GPIO3") (class "Default")
      (node (ref "U$2") (pin "P$35") (pinfunction "GPIO3_P$35") (pintype "bidirectional"))
      (node (ref "U$3") (pin "P$35") (pinfunction "GPIO3_P$35") (pintype "bidirectional"))
    )
    (net (code "17") (name "GPIO4") (class "Default")
      (node (ref "U$2") (pin "P$36") (pinfunction "GPIO4_P$36") (pintype "bidirectional"))
      (node (ref "U$3") (pin "P$36") (pinfunction "GPIO4_P$36") (pintype "bidirectional"))
    )
    (net (code "18") (name "GPIO5") (class "Default")
      (node (ref "U$2") (pin "P$37") (pinfunction "GPIO5_P$37") (pintype "bidirectional"))
      (node (ref "U$3") (pin "P$37") (pinfunction "GPIO5_P$37") (pintype "bidirectional"))
    )
    (net (code "19") (name "GPIO6") (class "Default")
      (node (ref "U$2") (pin "P$38") (pinfunction "GPIO6_P$38") (pintype "bidirectional"))
      (node (ref "U$3") (pin "P$38") (pinfunction "GPIO6_P$38") (pintype "bidirectional"))
    )
    (net (code "20") (name "GPIO7") (class "Default")
      (node (ref "U$2") (pin "P$39") (pinfunction "GPIO7_P$39") (pintype "bidirectional"))
      (node (ref "U$3") (pin "P$39") (pinfunction "GPIO7_P$39") (pintype "bidirectional"))
    )
    (net (code "21") (name "GPIO8") (class "Default")
      (node (ref "U$2") (pin "P$40") (pinfunction "GPIO8_P$40") (pintype "bidirectional"))
      (node (ref "U$3") (pin "P$40") (pinfunction "GPIO8_P$40") (pintype "bidirectional"))
    )
    (net (code "22") (name "GPIO9") (class "Default")
      (node (ref "U$2") (pin "P$41") (pinfunction "GPIO9_P$41") (pintype "bidirectional"))
      (node (ref "U$3") (pin "P$41") (pinfunction "GPIO9_P$41") (pintype "bidirectional"))
    )
    (net (code "23") (name "GPIO10") (class "Default")
      (node (ref "U$2") (pin "P$42") (pinfunction "GPIO10_P$42") (pintype "bidirectional"))
      (node (ref "U$3") (pin "P$42") (pinfunction "GPIO10_P$42") (pintype "bidirectional"))
    )
    (net (code "24") (name "GPIO11") (class "Default")
      (node (ref "U$2") (pin "P$43") (pinfunction "GPIO11_P$43") (pintype "bidirectional"))
      (node (ref "U$3") (pin "P$43") (pinfunction "GPIO11_P$43") (pintype "bidirectional"))
    )
    (net (code "25") (name "GPIO12") (class "Default")
      (node (ref "U$2") (pin "P$44") (pinfunction "GPIO12_P$44") (pintype "bidirectional"))
      (node (ref "U$3") (pin "P$44") (pinfunction "GPIO12_P$44") (pintype "bidirectional"))
    )
    (net (code "26") (name "MISO") (class "Default")
      (node (ref "U$2") (pin "P$32") (pinfunction "MISO_P$32") (pintype "bidirectional"))
      (node (ref "U$3") (pin "P$32") (pinfunction "MISO_P$32") (pintype "bidirectional"))
    )
    (net (code "27") (name "MOSI") (class "Default")
      (node (ref "U$2") (pin "P$31") (pinfunction "MOSI_P$31") (pintype "bidirectional"))
      (node (ref "U$3") (pin "P$31") (pinfunction "MOSI_P$31") (pintype "bidirectional"))
    )
    (net (code "28") (name "Net-(U$4-P$1)") (class "Default")
      (node (ref "U$4") (pin "P1") (pinfunction "P$1_P1") (pintype "bidirectional"))
      (node (ref "U13") (pin "5") (pinfunction "INB_5") (pintype "power_in"))
    )
    (net (code "29") (name "Net-(U$5-P$1)") (class "Default")
      (node (ref "U$5") (pin "P1") (pinfunction "P$1_P1") (pintype "bidirectional"))
      (node (ref "U13") (pin "1") (pinfunction "INA_1") (pintype "power_in"))
    )
    (net (code "30") (name "Net-(U$6-P$1)") (class "Default")
      (node (ref "U$6") (pin "P1") (pinfunction "P$1_P1") (pintype "bidirectional"))
      (node (ref "U16") (pin "1") (pinfunction "INA_1") (pintype "power_in"))
    )
    (net (code "31") (name "Net-(U$7-P$1)") (class "Default")
      (node (ref "U$7") (pin "P1") (pinfunction "P$1_P1") (pintype "bidirectional"))
      (node (ref "U16") (pin "5") (pinfunction "INB_5") (pintype "power_in"))
    )
    (net (code "32") (name "Net-(U$8-P$1)") (class "Default")
      (node (ref "U$8") (pin "P1") (pinfunction "P$1_P1") (pintype "bidirectional"))
      (node (ref "U19") (pin "5") (pinfunction "INB_5") (pintype "power_in"))
    )
    (net (code "33") (name "Net-(U$9-P$1)") (class "Default")
      (node (ref "U$9") (pin "P1") (pinfunction "P$1_P1") (pintype "bidirectional"))
      (node (ref "U19") (pin "1") (pinfunction "INA_1") (pintype "power_in"))
    )
    (net (code "34") (name "Net-(U$10-P$1)") (class "Default")
      (node (ref "U$10") (pin "P1") (pinfunction "P$1_P1") (pintype "bidirectional"))
      (node (ref "U$11") (pin "P1") (pinfunction "P$1_P1") (pintype "bidirectional"))
      (node (ref "U9") (pin "10") (pinfunction "BAT_10") (pintype "bidirectional"))
    )
    (net (code "35") (name "Net-(U$11-P$2)") (class "Default")
      (node (ref "R19") (pin "2") (pinfunction "2_2") (pintype "passive"))
      (node (ref "U$11") (pin "P2") (pinfunction "P$2_P2") (pintype "bidirectional"))
      (node (ref "U9") (pin "5") (pinfunction "TS_5") (pintype "input"))
    )
    (net (code "36") (name "Net-(U1-AUX)") (class "Default")
      (node (ref "C16") (pin "1") (pinfunction "1_1") (pintype "passive"))
      (node (ref "U1") (pin "10") (pinfunction "AUX_10") (pintype "passive"))
    )
    (net (code "37") (name "Net-(U1-FB)") (class "Default")
      (node (ref "R11") (pin "1") (pinfunction "1_1") (pintype "passive"))
      (node (ref "R12") (pin "2") (pinfunction "2_2") (pintype "passive"))
      (node (ref "U1") (pin "1") (pinfunction "FB_1") (pintype "input"))
    )
    (net (code "38") (name "Net-(U1-LDO)") (class "Default")
      (node (ref "C11") (pin "1") (pinfunction "1_1") (pintype "passive"))
      (node (ref "U1") (pin "2") (pinfunction "LDO_2") (pintype "output"))
    )
    (net (code "39") (name "Net-(U1-MPPC)") (class "Default")
      (node (ref "R17") (pin "2") (pinfunction "2_2") (pintype "passive"))
      (node (ref "U1") (pin "5") (pinfunction "MPPC_5") (pintype "input"))
    )
    (net (code "40") (name "Net-(U1-SW)") (class "Default")
      (node (ref "L1") (pin "1") (pinfunction "1_1") (pintype "passive"))
      (node (ref "U1") (pin "7") (pinfunction "SW_7") (pintype "passive"))
    )
    (net (code "41") (name "Net-(U1-VOUT)") (class "Default")
      (node (ref "C4") (pin "1") (pinfunction "1_1") (pintype "passive"))
      (node (ref "R11") (pin "2") (pinfunction "2_2") (pintype "passive"))
      (node (ref "U1") (pin "9") (pinfunction "VOUT_9") (pintype "output"))
      (node (ref "U4") (pin "1") (pinfunction "INA_1") (pintype "power_in"))
    )
    (net (code "42") (name "Net-(U2-AUX)") (class "Default")
      (node (ref "C14") (pin "1") (pinfunction "1_1") (pintype "passive"))
      (node (ref "U2") (pin "10") (pinfunction "AUX_10") (pintype "passive"))
    )
    (net (code "43") (name "Net-(U2-FB)") (class "Default")
      (node (ref "R10") (pin "2") (pinfunction "2_2") (pintype "passive"))
      (node (ref "R9") (pin "1") (pinfunction "1_1") (pintype "passive"))
      (node (ref "U2") (pin "1") (pinfunction "FB_1") (pintype "input"))
    )
    (net (code "44") (name "Net-(U2-LDO)") (class "Default")
      (node (ref "C12") (pin "1") (pinfunction "1_1") (pintype "passive"))
      (node (ref "U2") (pin "2") (pinfunction "LDO_2") (pintype "output"))
    )
    (net (code "45") (name "Net-(U2-MPPC)") (class "Default")
      (node (ref "R15") (pin "2") (pinfunction "2_2") (pintype "passive"))
      (node (ref "U2") (pin "5") (pinfunction "MPPC_5") (pintype "input"))
    )
    (net (code "46") (name "Net-(U2-SW)") (class "Default")
      (node (ref "L2") (pin "1") (pinfunction "1_1") (pintype "passive"))
      (node (ref "U2") (pin "7") (pinfunction "SW_7") (pintype "passive"))
    )
    (net (code "47") (name "Net-(U2-VOUT)") (class "Default")
      (node (ref "C5") (pin "1") (pinfunction "1_1") (pintype "passive"))
      (node (ref "R9") (pin "2") (pinfunction "2_2") (pintype "passive"))
      (node (ref "U2") (pin "9") (pinfunction "VOUT_9") (pintype "output"))
      (node (ref "U4") (pin "5") (pinfunction "INB_5") (pintype "power_in"))
    )
    (net (code "48") (name "Net-(U3-AUX)") (class "Default")
      (node (ref "C15") (pin "1") (pinfunction "1_1") (pintype "passive"))
      (node (ref "U3") (pin "10") (pinfunction "AUX_10") (pintype "passive"))
    )
    (net (code "49") (name "Net-(U3-FB)") (class "Default")
      (node (ref "R13") (pin "2") (pinfunction "2_2") (pintype "passive"))
      (node (ref "R14") (pin "1") (pinfunction "1_1") (pintype "passive"))
      (node (ref "U3") (pin "1") (pinfunction "FB_1") (pintype "input"))
    )
    (net (code "50") (name "Net-(U3-LDO)") (class "Default")
      (node (ref "C13") (pin "1") (pinfunction "1_1") (pintype "passive"))
      (node (ref "U3") (pin "2") (pinfunction "LDO_2") (pintype "output"))
    )
    (net (code "51") (name "Net-(U3-MPPC)") (class "Default")
      (node (ref "R16") (pin "2") (pinfunction "2_2") (pintype "passive"))
      (node (ref "U3") (pin "5") (pinfunction "MPPC_5") (pintype "input"))
    )
    (net (code "52") (name "Net-(U3-SW)") (class "Default")
      (node (ref "L3") (pin "1") (pinfunction "1_1") (pintype "passive"))
      (node (ref "U3") (pin "7") (pinfunction "SW_7") (pintype "passive"))
    )
    (net (code "53") (name "Net-(U3-VOUT)") (class "Default")
      (node (ref "C6") (pin "1") (pinfunction "1_1") (pintype "passive"))
      (node (ref "R14") (pin "2") (pinfunction "2_2") (pintype "passive"))
      (node (ref "U3") (pin "9") (pinfunction "VOUT_9") (pintype "output"))
      (node (ref "U5") (pin "5") (pinfunction "INB_5") (pintype "power_in"))
    )
    (net (code "54") (name "Net-(U4-OUTA)") (class "Default")
      (node (ref "C7") (pin "2") (pinfunction "2_2") (pintype "passive"))
      (node (ref "U4") (pin "10") (pinfunction "OUTA_10") (pintype "output"))
      (node (ref "U4") (pin "6") (pinfunction "OUTB_6") (pintype "output"))
      (node (ref "U5") (pin "1") (pinfunction "INA_1") (pintype "power_in"))
    )
    (net (code "55") (name "Net-(U4-STAT)") (class "Default")
      (node (ref "R2") (pin "1") (pinfunction "1_1") (pintype "passive"))
      (node (ref "U4") (pin "9") (pinfunction "STAT_9") (pintype "output"))
    )
    (net (code "56") (name "Net-(U5-OUTA)") (class "Default")
      (node (ref "C8") (pin "2") (pinfunction "2_2") (pintype "passive"))
      (node (ref "U5") (pin "10") (pinfunction "OUTA_10") (pintype "output"))
      (node (ref "U5") (pin "6") (pinfunction "OUTB_6") (pintype "output"))
      (node (ref "U9") (pin "1") (pinfunction "VBUS_1") (pintype "bidirectional"))
    )
    (net (code "57") (name "Net-(U5-STAT)") (class "Default")
      (node (ref "R1") (pin "1") (pinfunction "1_1") (pintype "passive"))
      (node (ref "U5") (pin "9") (pinfunction "STAT_9") (pintype "output"))
    )
    (net (code "58") (name "Net-(U6-L1)") (class "Default")
      (node (ref "L4") (pin "1") (pinfunction "1_1") (pintype "passive"))
      (node (ref "U6") (pin "4") (pinfunction "L1_4") (pintype "passive"))
    )
    (net (code "59") (name "Net-(U6-L2)") (class "Default")
      (node (ref "L4") (pin "2") (pinfunction "2_2") (pintype "passive"))
      (node (ref "U6") (pin "2") (pinfunction "L2_2") (pintype "passive"))
    )
    (net (code "60") (name "Net-(U7-EN)") (class "Default")
      (node (ref "C17") (pin "1") (pinfunction "1_1") (pintype "passive"))
      (node (ref "R3") (pin "1") (pinfunction "1_1") (pintype "passive"))
      (node (ref "U7") (pin "P$3") (pinfunction "~{FAULT}_P$3") (pintype "output"))
      (node (ref "U7") (pin "P$4") (pinfunction "EN_P$4") (pintype "input"))
    )
    (net (code "61") (name "Net-(U7-ILIM)") (class "Default")
      (node (ref "R4") (pin "1") (pinfunction "1_1") (pintype "passive"))
      (node (ref "U7") (pin "P$2") (pinfunction "ILIM_P$2") (pintype "input"))
    )
    (net (code "62") (name "Net-(U8-EN)") (class "Default")
      (node (ref "C25") (pin "1") (pinfunction "1_1") (pintype "passive"))
      (node (ref "R5") (pin "1") (pinfunction "1_1") (pintype "passive"))
      (node (ref "U8") (pin "P$3") (pinfunction "~{FAULT}_P$3") (pintype "output"))
      (node (ref "U8") (pin "P$4") (pinfunction "EN_P$4") (pintype "input"))
    )
    (net (code "63") (name "Net-(U8-ILIM)") (class "Default")
      (node (ref "R6") (pin "1") (pinfunction "1_1") (pintype "passive"))
      (node (ref "U8") (pin "P$2") (pinfunction "ILIM_P$2") (pintype "input"))
    )
    (net (code "64") (name "Net-(U9-ISET)") (class "Default")
      (node (ref "R18") (pin "2") (pinfunction "2_2") (pintype "passive"))
      (node (ref "U9") (pin "2") (pinfunction "ISET_2") (pintype "input"))
    )
    (net (code "65") (name "Net-(U9-VTSB)") (class "Default")
      (node (ref "R19") (pin "1") (pinfunction "1_1") (pintype "passive"))
      (node (ref "U9") (pin "4") (pinfunction "VTSB_4") (pintype "output"))
    )
    (net (code "66") (name "Net-(U9-~{EN})") (class "Default")
      (node (ref "U9") (pin "6") (pinfunction "~{PG}_6") (pintype "output"))
      (node (ref "U9") (pin "7") (pinfunction "~{EN}_7") (pintype "input"))
    )
    (net (code "67") (name "Net-(U11-EN)") (class "Default")
      (node (ref "C24") (pin "1") (pinfunction "1_1") (pintype "passive"))
      (node (ref "R8") (pin "2") (pinfunction "2_2") (pintype "passive"))
      (node (ref "U11") (pin "P$3") (pinfunction "~{FAULT}_P$3") (pintype "output"))
      (node (ref "U11") (pin "P$4") (pinfunction "EN_P$4") (pintype "input"))
    )
    (net (code "68") (name "Net-(U11-ILIM)") (class "Default")
      (node (ref "R7") (pin "1") (pinfunction "1_1") (pintype "passive"))
      (node (ref "U11") (pin "P$2") (pinfunction "ILIM_P$2") (pintype "input"))
    )
    (net (code "69") (name "Net-(U12-EN)") (class "Default")
      (node (ref "C20") (pin "1") (pinfunction "1_1") (pintype "passive"))
      (node (ref "R21") (pin "2") (pinfunction "2_2") (pintype "passive"))
      (node (ref "U12") (pin "P$3") (pinfunction "~{FAULT}_P$3") (pintype "output"))
      (node (ref "U12") (pin "P$4") (pinfunction "EN_P$4") (pintype "input"))
    )
    (net (code "70") (name "Net-(U12-ILIM)") (class "Default")
      (node (ref "R20") (pin "1") (pinfunction "1_1") (pintype "passive"))
      (node (ref "U12") (pin "P$2") (pinfunction "ILIM_P$2") (pintype "input"))
    )
    (net (code "71") (name "Net-(U13-STAT)") (class "Default")
      (node (ref "R22") (pin "1") (pinfunction "1_1") (pintype "passive"))
      (node (ref "U13") (pin "9") (pinfunction "STAT_9") (pintype "output"))
    )
    (net (code "72") (name "Net-(U14-EN)") (class "Default")
      (node (ref "C19") (pin "1") (pinfunction "1_1") (pintype "passive"))
      (node (ref "R25") (pin "2") (pinfunction "2_2") (pintype "passive"))
      (node (ref "U14") (pin "P$3") (pinfunction "~{FAULT}_P$3") (pintype "output"))
      (node (ref "U14") (pin "P$4") (pinfunction "EN_P$4") (pintype "input"))
    )
    (net (code "73") (name "Net-(U14-ILIM)") (class "Default")
      (node (ref "R24") (pin "1") (pinfunction "1_1") (pintype "passive"))
      (node (ref "U14") (pin "P$2") (pinfunction "ILIM_P$2") (pintype "input"))
    )
    (net (code "74") (name "Net-(U15-EN)") (class "Default")
      (node (ref "C33") (pin "1") (pinfunction "1_1") (pintype "passive"))
      (node (ref "R27") (pin "2") (pinfunction "2_2") (pintype "passive"))
      (node (ref "U15") (pin "P$3") (pinfunction "~{FAULT}_P$3") (pintype "output"))
      (node (ref "U15") (pin "P$4") (pinfunction "EN_P$4") (pintype "input"))
    )
    (net (code "75") (name "Net-(U15-ILIM)") (class "Default")
      (node (ref "R26") (pin "1") (pinfunction "1_1") (pintype "passive"))
      (node (ref "U15") (pin "P$2") (pinfunction "ILIM_P$2") (pintype "input"))
    )
    (net (code "76") (name "Net-(U16-STAT)") (class "Default")
      (node (ref "R23") (pin "1") (pinfunction "1_1") (pintype "passive"))
      (node (ref "U16") (pin "9") (pinfunction "STAT_9") (pintype "output"))
    )
    (net (code "77") (name "Net-(U17-EN)") (class "Default")
      (node (ref "C27") (pin "1") (pinfunction "1_1") (pintype "passive"))
      (node (ref "R30") (pin "2") (pinfunction "2_2") (pintype "passive"))
      (node (ref "U17") (pin "P$3") (pinfunction "~{FAULT}_P$3") (pintype "output"))
      (node (ref "U17") (pin "P$4") (pinfunction "EN_P$4") (pintype "input"))
    )
    (net (code "78") (name "Net-(U17-ILIM)") (class "Default")
      (node (ref "R31") (pin "1") (pinfunction "1_1") (pintype "passive"))
      (node (ref "U17") (pin "P$2") (pinfunction "ILIM_P$2") (pintype "input"))
    )
    (net (code "79") (name "Net-(U18-EN)") (class "Default")
      (node (ref "C31") (pin "1") (pinfunction "1_1") (pintype "passive"))
      (node (ref "R33") (pin "2") (pinfunction "2_2") (pintype "passive"))
      (node (ref "U18") (pin "P$3") (pinfunction "~{FAULT}_P$3") (pintype "output"))
      (node (ref "U18") (pin "P$4") (pinfunction "EN_P$4") (pintype "input"))
    )
    (net (code "80") (name "Net-(U18-ILIM)") (class "Default")
      (node (ref "R32") (pin "1") (pinfunction "1_1") (pintype "passive"))
      (node (ref "U18") (pin "P$2") (pinfunction "ILIM_P$2") (pintype "input"))
    )
    (net (code "81") (name "Net-(U19-STAT)") (class "Default")
      (node (ref "R28") (pin "1") (pinfunction "1_1") (pintype "passive"))
      (node (ref "U19") (pin "9") (pinfunction "STAT_9") (pintype "output"))
    )
    (net (code "82") (name "PANEL1+2") (class "Default")
      (node (ref "C21") (pin "2") (pinfunction "2_2") (pintype "passive"))
      (node (ref "C3") (pin "2") (pinfunction "2_2") (pintype "passive"))
      (node (ref "L1") (pin "2") (pinfunction "2_2") (pintype "passive"))
      (node (ref "U1") (pin "6") (pinfunction "VIN_6") (pintype "power_in"))
      (node (ref "U13") (pin "10") (pinfunction "OUTA_10") (pintype "output"))
      (node (ref "U13") (pin "6") (pinfunction "OUTB_6") (pintype "output"))
    )
    (net (code "83") (name "PANEL3+4") (class "Default")
      (node (ref "C2") (pin "2") (pinfunction "2_2") (pintype "passive"))
      (node (ref "C22") (pin "2") (pinfunction "2_2") (pintype "passive"))
      (node (ref "L2") (pin "2") (pinfunction "2_2") (pintype "passive"))
      (node (ref "U16") (pin "10") (pinfunction "OUTA_10") (pintype "output"))
      (node (ref "U16") (pin "6") (pinfunction "OUTB_6") (pintype "output"))
      (node (ref "U2") (pin "6") (pinfunction "VIN_6") (pintype "power_in"))
    )
    (net (code "84") (name "PANEL5+6") (class "Default")
      (node (ref "C1") (pin "2") (pinfunction "2_2") (pintype "passive"))
      (node (ref "C35") (pin "2") (pinfunction "2_2") (pintype "passive"))
      (node (ref "L3") (pin "2") (pinfunction "2_2") (pintype "passive"))
      (node (ref "U19") (pin "10") (pinfunction "OUTA_10") (pintype "output"))
      (node (ref "U19") (pin "6") (pinfunction "OUTB_6") (pintype "output"))
      (node (ref "U3") (pin "6") (pinfunction "VIN_6") (pintype "power_in"))
    )
    (net (code "85") (name "SCK") (class "Default")
      (node (ref "U$2") (pin "P$33") (pinfunction "SCK_P$33") (pintype "bidirectional"))
      (node (ref "U$3") (pin "P$33") (pinfunction "SCK_P$33") (pintype "bidirectional"))
    )
    (net (code "86") (name "SCL") (class "Default")
      (node (ref "U$2") (pin "P$29") (pinfunction "SCL_P$29") (pintype "bidirectional"))
      (node (ref "U$3") (pin "P$29") (pinfunction "SCL_P$29") (pintype "bidirectional"))
      (node (ref "U10") (pin "14") (pinfunction "SCL_14") (pintype "bidirectional"))
    )
    (net (code "87") (name "SDA") (class "Default")
      (node (ref "U$2") (pin "P$30") (pinfunction "SDA_P$30") (pintype "bidirectional"))
      (node (ref "U$3") (pin "P$30") (pinfunction "SDA_P$30") (pintype "bidirectional"))
      (node (ref "U10") (pin "15") (pinfunction "SDA_15") (pintype "bidirectional"))
    )
    (net (code "88") (name "SW1_EN") (class "Default")
      (node (ref "R25") (pin "1") (pinfunction "1_1") (pintype "passive"))
      (node (ref "U10") (pin "4") (pinfunction "IO0_4") (pintype "bidirectional"))
    )
    (net (code "89") (name "SW2_EN") (class "Default")
      (node (ref "R33") (pin "1") (pinfunction "1_1") (pintype "passive"))
      (node (ref "U10") (pin "5") (pinfunction "IO1_5") (pintype "bidirectional"))
    )
    (net (code "90") (name "SW3_EN") (class "Default")
      (node (ref "R27") (pin "1") (pinfunction "1_1") (pintype "passive"))
      (node (ref "U10") (pin "6") (pinfunction "IO2_6") (pintype "bidirectional"))
    )
    (net (code "91") (name "SW4_EN") (class "Default")
      (node (ref "R30") (pin "1") (pinfunction "1_1") (pintype "passive"))
      (node (ref "U10") (pin "7") (pinfunction "IO3_7") (pintype "bidirectional"))
    )
    (net (code "92") (name "SW5_EN") (class "Default")
      (node (ref "R8") (pin "1") (pinfunction "1_1") (pintype "passive"))
      (node (ref "U10") (pin "9") (pinfunction "IO4_9") (pintype "bidirectional"))
    )
    (net (code "93") (name "SW6_EN") (class "Default")
      (node (ref "R21") (pin "1") (pinfunction "1_1") (pintype "passive"))
      (node (ref "U10") (pin "10") (pinfunction "IO5_10") (pintype "bidirectional"))
    )
    (net (code "94") (name "UNPROTECTED3V3") (class "Default")
      (node (ref "C10") (pin "2") (pinfunction "2_2") (pintype "passive"))
      (node (ref "C26") (pin "2") (pinfunction "2_2") (pintype "passive"))
      (node (ref "C29") (pin "2") (pinfunction "2_2") (pintype "passive"))
      (node (ref "C32") (pin "2") (pinfunction "2_2") (pintype "passive"))
      (node (ref "C34") (pin "2") (pinfunction "2_2") (pintype "passive"))
      (node (ref "R5") (pin "2") (pinfunction "2_2") (pintype "passive"))
      (node (ref "U14") (pin "P$6") (pinfunction "IN_P$6") (pintype "power_in"))
      (node (ref "U15") (pin "P$6") (pinfunction "IN_P$6") (pintype "power_in"))
      (node (ref "U18") (pin "P$6") (pinfunction "IN_P$6") (pintype "power_in"))
      (node (ref "U6") (pin "1") (pinfunction "VOUT_1") (pintype "output"))
      (node (ref "U6") (pin "10") (pinfunction "FB_10") (pintype "input"))
      (node (ref "U8") (pin "P$6") (pinfunction "IN_P$6") (pintype "power_in"))
    )
    (net (code "95") (name "unconnected-(U1-PGOOD-Pad8)") (class "Default")
      (node (ref "U1") (pin "8") (pinfunction "PGOOD_8") (pintype "output"))
    )
    (net (code "96") (name "unconnected-(U2-PGOOD-Pad8)") (class "Default")
      (node (ref "U2") (pin "8") (pinfunction "PGOOD_8") (pintype "output"))
    )
    (net (code "97") (name "unconnected-(U3-PGOOD-Pad8)") (class "Default")
      (node (ref "U3") (pin "8") (pinfunction "PGOOD_8") (pintype "output"))
    )
    (net (code "98") (name "unconnected-(U4-NC-Pad7)") (class "Default")
      (node (ref "U4") (pin "7") (pinfunction "NC_7") (pintype "no_connect"))
    )
    (net (code "99") (name "unconnected-(U4-NC_2-Pad8)") (class "Default")
      (node (ref "U4") (pin "8") (pinfunction "NC_2_8") (pintype "no_connect"))
    )
    (net (code "100") (name "unconnected-(U5-NC-Pad7)") (class "Default")
      (node (ref "U5") (pin "7") (pinfunction "NC_7") (pintype "no_connect"))
    )
    (net (code "101") (name "unconnected-(U5-NC_2-Pad8)") (class "Default")
      (node (ref "U5") (pin "8") (pinfunction "NC_2_8") (pintype "no_connect"))
    )
    (net (code "102") (name "unconnected-(U9-VDPM-Pad9)") (class "Default")
      (node (ref "U9") (pin "9") (pinfunction "VDPM_9") (pintype "input"))
    )
    (net (code "103") (name "unconnected-(U10-A0-Pad1)") (class "Default")
      (node (ref "U10") (pin "1") (pinfunction "A0_1") (pintype "input"))
    )
    (net (code "104") (name "unconnected-(U10-A1-Pad2)") (class "Default")
      (node (ref "U10") (pin "2") (pinfunction "A1_2") (pintype "input"))
    )
    (net (code "105") (name "unconnected-(U10-A2-Pad3)") (class "Default")
      (node (ref "U10") (pin "3") (pinfunction "A2_3") (pintype "input"))
    )
    (net (code "106") (name "unconnected-(U10-IO7-Pad12)") (class "Default")
      (node (ref "U10") (pin "12") (pinfunction "IO7_12") (pintype "bidirectional"))
    )
    (net (code "107") (name "unconnected-(U10-~{INT}-Pad13)") (class "Default")
      (node (ref "U10") (pin "13") (pinfunction "~{INT}_13") (pintype "output"))
    )
    (net (code "108") (name "unconnected-(U13-NC-Pad7)") (class "Default")
      (node (ref "U13") (pin "7") (pinfunction "NC_7") (pintype "no_connect"))
    )
    (net (code "109") (name "unconnected-(U13-NC_2-Pad8)") (class "Default")
      (node (ref "U13") (pin "8") (pinfunction "NC_2_8") (pintype "no_connect"))
    )
    (net (code "110") (name "unconnected-(U16-NC-Pad7)") (class "Default")
      (node (ref "U16") (pin "7") (pinfunction "NC_7") (pintype "no_connect"))
    )
    (net (code "111") (name "unconnected-(U16-NC_2-Pad8)") (class "Default")
      (node (ref "U16") (pin "8") (pinfunction "NC_2_8") (pintype "no_connect"))
    )
    (net (code "112") (name "unconnected-(U19-NC-Pad7)") (class "Default")
      (node (ref "U19") (pin "7") (pinfunction "NC_7") (pintype "no_connect"))
    )
    (net (code "113") (name "unconnected-(U19-NC_2-Pad8)") (class "Default")
      (node (ref "U19") (pin "8") (pinfunction "NC_2_8") (pintype "no_connect"))
    )
  )
)
